# PCB_SCH_Left_Sub.net
KiCad netlist of a schematic drawn in EasyEDA Pro
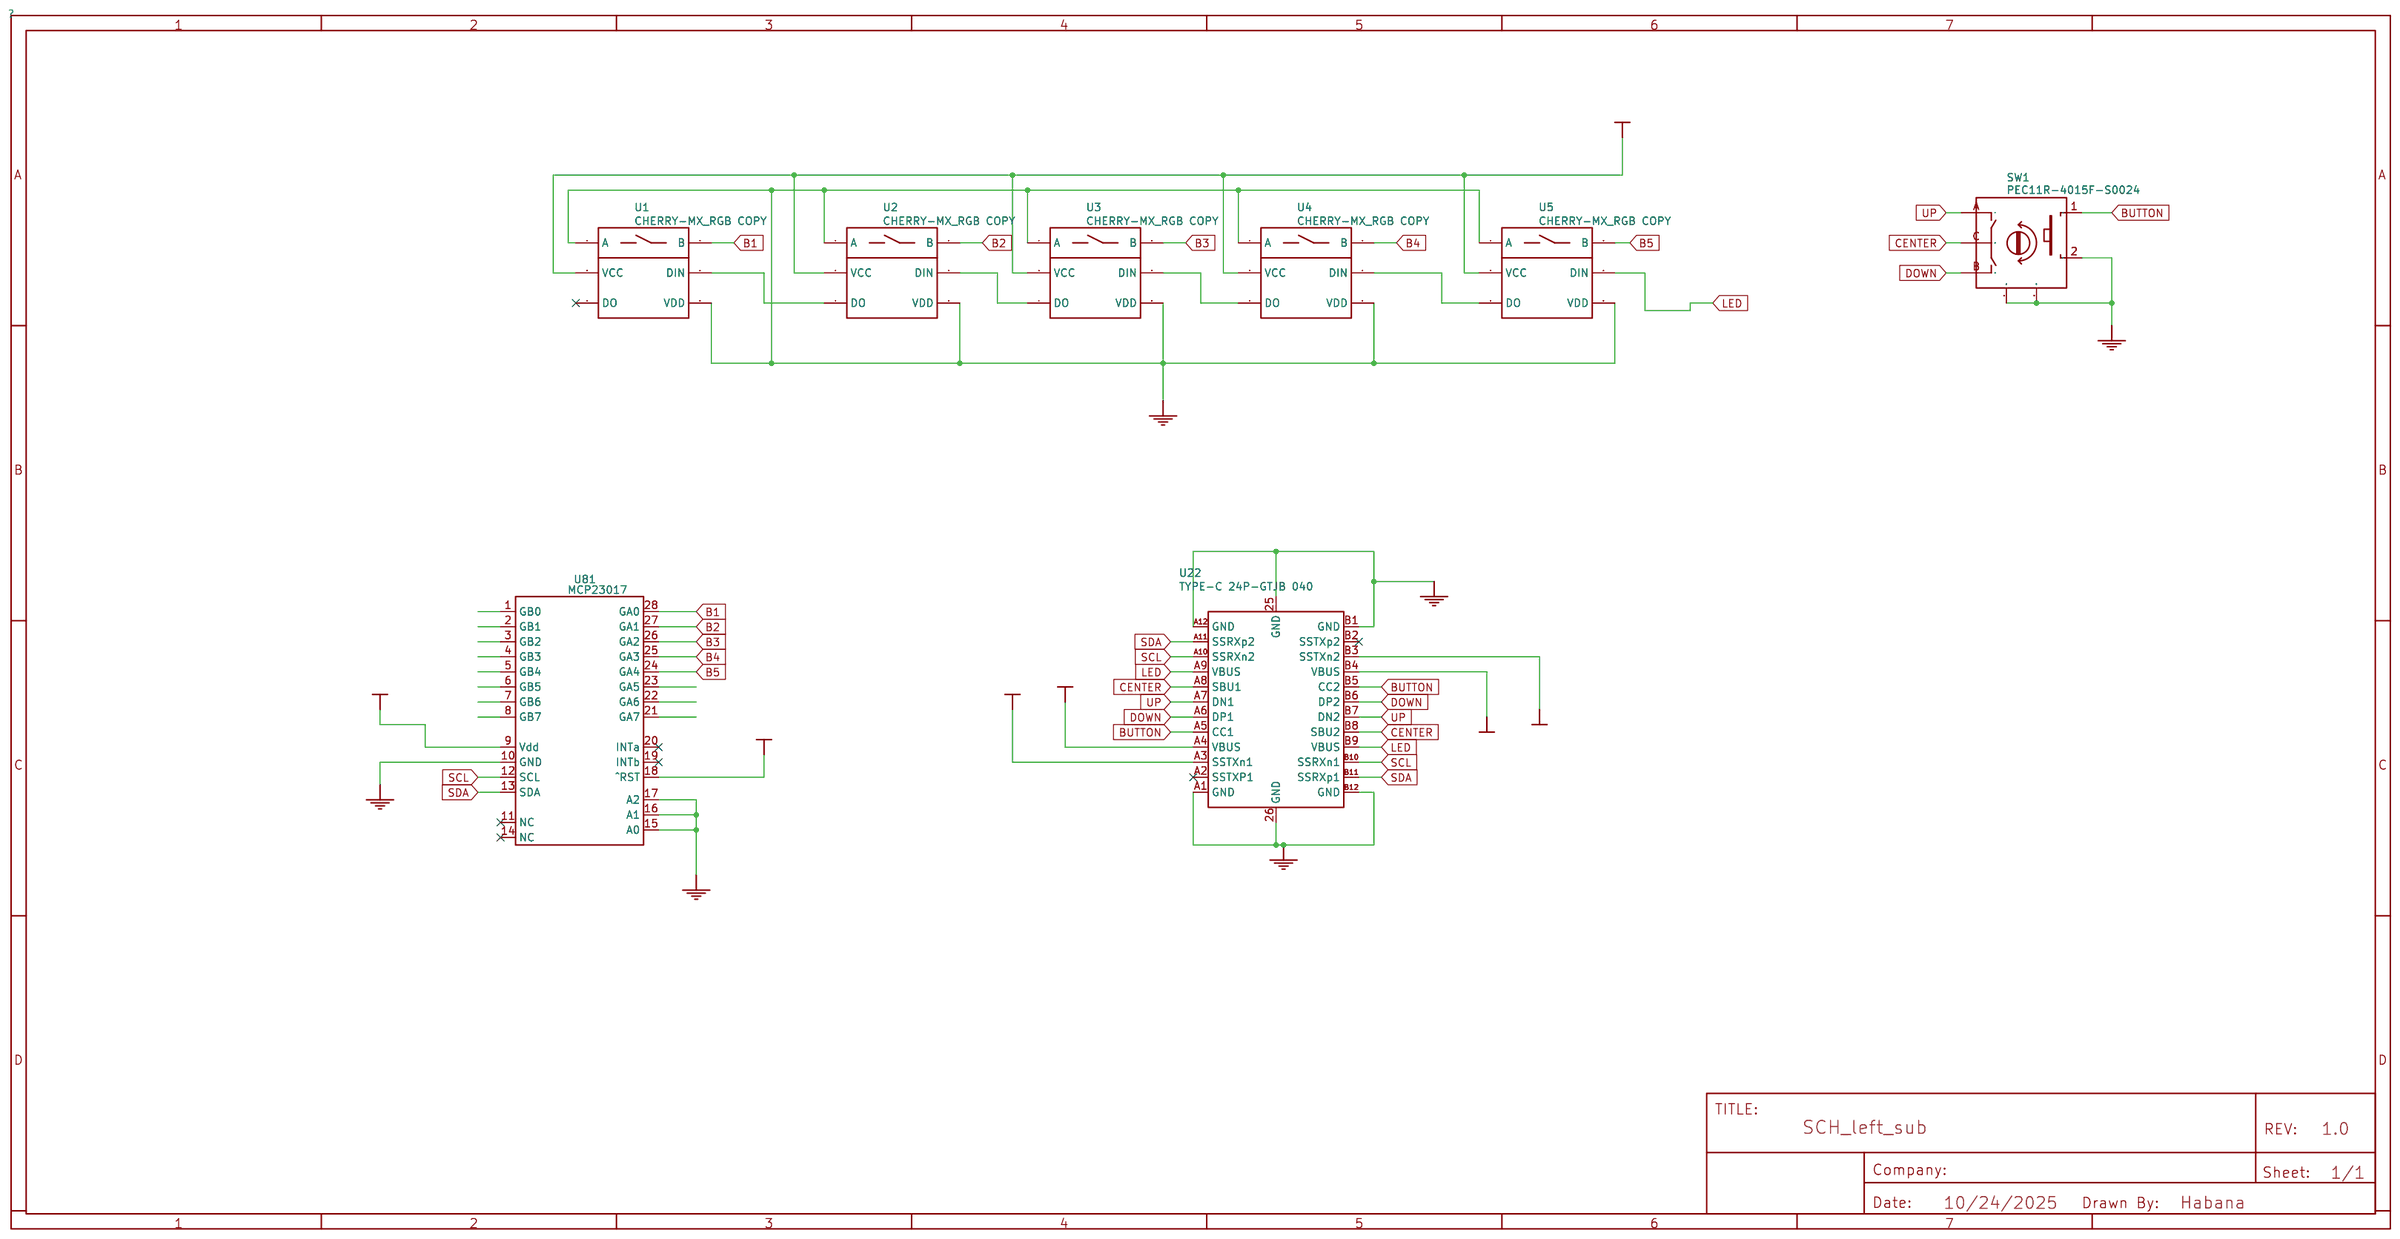
[diagram p0: schematic sheet]

(export (version "E")
  (design (tool "Eeschema 10.0.6"))
  (components
    (comp (ref "SW1")
      (value "PEC11R-4015F-S0024")
      (footprint "easyedapro:SW-TH_PEC11R-4XXXF-SXXXX")
      (fields (field (name "Manufacturer") "BOURNS") (field (name "Contributor") "LCSC"))
      (libsource (lib "easyedapro") (part "PEC11R-4015F-S0024"))
    )
    (comp (ref "U1")
      (value "CHERRY-MX_RGB COPY")
      (fields (field (name "Contributor") "unrealin01"))
      (libsource (lib "easyedapro") (part "CHERRY-MX_RGB COPY"))
    )
    (comp (ref "U2")
      (value "CHERRY-MX_RGB COPY")
      (fields (field (name "Contributor") "unrealin01"))
      (libsource (lib "easyedapro") (part "CHERRY-MX_RGB COPY"))
    )
    (comp (ref "U3")
      (value "CHERRY-MX_RGB COPY")
      (fields (field (name "Contributor") "unrealin01"))
      (libsource (lib "easyedapro") (part "CHERRY-MX_RGB COPY"))
    )
    (comp (ref "U4")
      (value "CHERRY-MX_RGB COPY")
      (fields (field (name "Contributor") "unrealin01"))
      (libsource (lib "easyedapro") (part "CHERRY-MX_RGB COPY"))
    )
    (comp (ref "U5")
      (value "CHERRY-MX_RGB COPY")
      (fields (field (name "Contributor") "unrealin01"))
      (libsource (lib "easyedapro") (part "CHERRY-MX_RGB COPY"))
    )
    (comp (ref "U22")
      (value "TYPE-C 24P-GTJB 040")
      (footprint "easyedapro:USB-C-SMD_TYPE-C-24P-GTJB-040")
      (fields (field (name "Manufacturer") "SHOU HAN(首韩)") (field (name "Contributor") "lcsc"))
      (libsource (lib "easyedapro") (part "TYPE-C 24P-GTJB 040"))
    )
    (comp (ref "U81")
      (value "MCP23017")
      (fields (field (name "Contributor") "tsvstar"))
      (libsource (lib "easyedapro") (part "MCP23017"))
    )
  )
  (nets
    (net (code "1") (name "+5V") (class "Default")
      (node (ref "U1") (pin "3") (pinfunction "VCC_3") (pintype "unspecified"))
      (node (ref "U2") (pin "3") (pinfunction "VCC_3") (pintype "unspecified"))
      (node (ref "U22") (pin "A4") (pinfunction "VBUS_A4") (pintype "unspecified"))
      (node (ref "U22") (pin "B4") (pinfunction "VBUS_B4") (pintype "unspecified"))
      (node (ref "U3") (pin "3") (pinfunction "VCC_3") (pintype "unspecified"))
      (node (ref "U4") (pin "3") (pinfunction "VCC_3") (pintype "unspecified"))
      (node (ref "U5") (pin "3") (pinfunction "VCC_3") (pintype "unspecified"))
    )
    (net (code "2") (name "B1") (class "Default")
      (node (ref "U1") (pin "2") (pinfunction "B_2") (pintype "unspecified"))
      (node (ref "U81") (pin "28") (pinfunction "GA0_28") (pintype "unspecified"))
    )
    (net (code "3") (name "B2") (class "Default")
      (node (ref "U2") (pin "2") (pinfunction "B_2") (pintype "unspecified"))
      (node (ref "U81") (pin "27") (pinfunction "GA1_27") (pintype "unspecified"))
    )
    (net (code "4") (name "B3") (class "Default")
      (node (ref "U3") (pin "2") (pinfunction "B_2") (pintype "unspecified"))
      (node (ref "U81") (pin "26") (pinfunction "GA2_26") (pintype "unspecified"))
    )
    (net (code "5") (name "B4") (class "Default")
      (node (ref "U4") (pin "2") (pinfunction "B_2") (pintype "unspecified"))
      (node (ref "U81") (pin "25") (pinfunction "GA3_25") (pintype "unspecified"))
    )
    (net (code "6") (name "B5") (class "Default")
      (node (ref "U5") (pin "2") (pinfunction "B_2") (pintype "unspecified"))
      (node (ref "U81") (pin "24") (pinfunction "GA4_24") (pintype "unspecified"))
    )
    (net (code "7") (name "BUTTON") (class "Default")
      (node (ref "SW1") (pin "1") (pinfunction "1_1") (pintype "unspecified"))
      (node (ref "U22") (pin "A5") (pinfunction "CC1_A5") (pintype "unspecified"))
      (node (ref "U22") (pin "B5") (pinfunction "CC2_B5") (pintype "unspecified"))
    )
    (net (code "8") (name "CENTER") (class "Default")
      (node (ref "SW1") (pin "C") (pinfunction "C_C") (pintype "unspecified"))
      (node (ref "U22") (pin "A8") (pinfunction "SBU1_A8") (pintype "unspecified"))
      (node (ref "U22") (pin "B8") (pinfunction "SBU2_B8") (pintype "unspecified"))
    )
    (net (code "9") (name "DOWN") (class "Default")
      (node (ref "SW1") (pin "B") (pinfunction "B_B") (pintype "unspecified"))
      (node (ref "U22") (pin "A6") (pinfunction "DP1_A6") (pintype "unspecified"))
      (node (ref "U22") (pin "B6") (pinfunction "DP2_B6") (pintype "unspecified"))
    )
    (net (code "10") (name "GND") (class "Default")
      (node (ref "SW1") (pin "2") (pinfunction "2_2") (pintype "unspecified"))
      (node (ref "SW1") (pin "MT1") (pinfunction "MT1_MT1") (pintype "unspecified"))
      (node (ref "SW1") (pin "MT2") (pinfunction "MT2_MT2") (pintype "unspecified"))
      (node (ref "U1") (pin "1") (pinfunction "A_1") (pintype "unspecified"))
      (node (ref "U1") (pin "5") (pinfunction "VDD_5") (pintype "unspecified"))
      (node (ref "U2") (pin "1") (pinfunction "A_1") (pintype "unspecified"))
      (node (ref "U2") (pin "5") (pinfunction "VDD_5") (pintype "unspecified"))
      (node (ref "U22") (pin "25") (pinfunction "GND_25") (pintype "unspecified"))
      (node (ref "U22") (pin "26") (pinfunction "GND_26") (pintype "unspecified"))
      (node (ref "U22") (pin "A1") (pinfunction "GND_A1") (pintype "unspecified"))
      (node (ref "U22") (pin "A12") (pinfunction "GND_A12") (pintype "unspecified"))
      (node (ref "U22") (pin "B1") (pinfunction "GND_B1") (pintype "unspecified"))
      (node (ref "U22") (pin "B12") (pinfunction "GND_B12") (pintype "unspecified"))
      (node (ref "U3") (pin "1") (pinfunction "A_1") (pintype "unspecified"))
      (node (ref "U3") (pin "5") (pinfunction "VDD_5") (pintype "unspecified"))
      (node (ref "U4") (pin "1") (pinfunction "A_1") (pintype "unspecified"))
      (node (ref "U4") (pin "5") (pinfunction "VDD_5") (pintype "unspecified"))
      (node (ref "U5") (pin "1") (pinfunction "A_1") (pintype "unspecified"))
      (node (ref "U5") (pin "5") (pinfunction "VDD_5") (pintype "unspecified"))
      (node (ref "U81") (pin "10") (pinfunction "GND_10") (pintype "unspecified"))
      (node (ref "U81") (pin "15") (pinfunction "A0_15") (pintype "unspecified"))
      (node (ref "U81") (pin "16") (pinfunction "A1_16") (pintype "unspecified"))
      (node (ref "U81") (pin "17") (pinfunction "A2_17") (pintype "unspecified"))
    )
    (net (code "11") (name "LED") (class "Default")
      (node (ref "U22") (pin "A9") (pinfunction "VBUS_A9") (pintype "unspecified"))
      (node (ref "U22") (pin "B9") (pinfunction "VBUS_B9") (pintype "unspecified"))
      (node (ref "U5") (pin "6") (pinfunction "DIN_6") (pintype "unspecified"))
    )
    (net (code "12") (name "Net-(U1-DIN)") (class "Default")
      (node (ref "U1") (pin "6") (pinfunction "DIN_6") (pintype "unspecified"))
      (node (ref "U2") (pin "4") (pinfunction "DO_4") (pintype "unspecified"))
    )
    (net (code "13") (name "Net-(U2-DIN)") (class "Default")
      (node (ref "U2") (pin "6") (pinfunction "DIN_6") (pintype "unspecified"))
      (node (ref "U3") (pin "4") (pinfunction "DO_4") (pintype "unspecified"))
    )
    (net (code "14") (name "Net-(U3-DIN)") (class "Default")
      (node (ref "U3") (pin "6") (pinfunction "DIN_6") (pintype "unspecified"))
      (node (ref "U4") (pin "4") (pinfunction "DO_4") (pintype "unspecified"))
    )
    (net (code "15") (name "Net-(U4-DIN)") (class "Default")
      (node (ref "U4") (pin "6") (pinfunction "DIN_6") (pintype "unspecified"))
      (node (ref "U5") (pin "4") (pinfunction "DO_4") (pintype "unspecified"))
    )
    (net (code "16") (name "SCL") (class "Default")
      (node (ref "U22") (pin "A10") (pinfunction "SSRXn2_A10") (pintype "unspecified"))
      (node (ref "U22") (pin "B10") (pinfunction "SSRXn1_B10") (pintype "unspecified"))
      (node (ref "U81") (pin "12") (pinfunction "SCL_12") (pintype "unspecified"))
    )
    (net (code "17") (name "SDA") (class "Default")
      (node (ref "U22") (pin "A11") (pinfunction "SSRXp2_A11") (pintype "unspecified"))
      (node (ref "U22") (pin "B11") (pinfunction "SSRXp1_B11") (pintype "unspecified"))
      (node (ref "U81") (pin "13") (pinfunction "SDA_13") (pintype "unspecified"))
    )
    (net (code "18") (name "UP") (class "Default")
      (node (ref "SW1") (pin "A") (pinfunction "A_A") (pintype "unspecified"))
      (node (ref "U22") (pin "A7") (pinfunction "DN1_A7") (pintype "unspecified"))
      (node (ref "U22") (pin "B7") (pinfunction "DN2_B7") (pintype "unspecified"))
    )
    (net (code "19") (name "VCC") (class "Default")
      (node (ref "U22") (pin "A3") (pinfunction "SSTXn1_A3") (pintype "unspecified"))
      (node (ref "U22") (pin "B3") (pinfunction "SSTXn2_B3") (pintype "unspecified"))
      (node (ref "U81") (pin "18") (pinfunction "^RST_18") (pintype "unspecified"))
      (node (ref "U81") (pin "9") (pinfunction "Vdd_9") (pintype "unspecified"))
    )
    (net (code "20") (name "unconnected-(U1-DO-Pad4)") (class "Default")
      (node (ref "U1") (pin "4") (pinfunction "DO_4") (pintype "unspecified+no_connect"))
    )
    (net (code "21") (name "unconnected-(U22-SSTXP1-PadA2)") (class "Default")
      (node (ref "U22") (pin "A2") (pinfunction "SSTXP1_A2") (pintype "unspecified+no_connect"))
    )
    (net (code "22") (name "unconnected-(U22-SSTXp2-PadB2)") (class "Default")
      (node (ref "U22") (pin "B2") (pinfunction "SSTXp2_B2") (pintype "unspecified+no_connect"))
    )
    (net (code "23") (name "unconnected-(U81-GA5-Pad23)") (class "Default")
      (node (ref "U81") (pin "23") (pinfunction "GA5_23") (pintype "unspecified"))
    )
    (net (code "24") (name "unconnected-(U81-GA6-Pad22)") (class "Default")
      (node (ref "U81") (pin "22") (pinfunction "GA6_22") (pintype "unspecified"))
    )
    (net (code "25") (name "unconnected-(U81-GA7-Pad21)") (class "Default")
      (node (ref "U81") (pin "21") (pinfunction "GA7_21") (pintype "unspecified"))
    )
    (net (code "26") (name "unconnected-(U81-GB0-Pad1)") (class "Default")
      (node (ref "U81") (pin "1") (pinfunction "GB0_1") (pintype "unspecified"))
    )
    (net (code "27") (name "unconnected-(U81-GB1-Pad2)") (class "Default")
      (node (ref "U81") (pin "2") (pinfunction "GB1_2") (pintype "unspecified"))
    )
    (net (code "28") (name "unconnected-(U81-GB2-Pad3)") (class "Default")
      (node (ref "U81") (pin "3") (pinfunction "GB2_3") (pintype "unspecified"))
    )
    (net (code "29") (name "unconnected-(U81-GB3-Pad4)") (class "Default")
      (node (ref "U81") (pin "4") (pinfunction "GB3_4") (pintype "unspecified"))
    )
    (net (code "30") (name "unconnected-(U81-GB4-Pad5)") (class "Default")
      (node (ref "U81") (pin "5") (pinfunction "GB4_5") (pintype "unspecified"))
    )
    (net (code "31") (name "unconnected-(U81-GB5-Pad6)") (class "Default")
      (node (ref "U81") (pin "6") (pinfunction "GB5_6") (pintype "unspecified"))
    )
    (net (code "32") (name "unconnected-(U81-GB6-Pad7)") (class "Default")
      (node (ref "U81") (pin "7") (pinfunction "GB6_7") (pintype "unspecified"))
    )
    (net (code "33") (name "unconnected-(U81-GB7-Pad8)") (class "Default")
      (node (ref "U81") (pin "8") (pinfunction "GB7_8") (pintype "unspecified"))
    )
    (net (code "34") (name "unconnected-(U81-INTa-Pad20)") (class "Default")
      (node (ref "U81") (pin "20") (pinfunction "INTa_20") (pintype "unspecified+no_connect"))
    )
    (net (code "35") (name "unconnected-(U81-INTb-Pad19)") (class "Default")
      (node (ref "U81") (pin "19") (pinfunction "INTb_19") (pintype "unspecified+no_connect"))
    )
    (net (code "36") (name "unconnected-(U81-NC-Pad11)") (class "Default")
      (node (ref "U81") (pin "11") (pinfunction "NC_11") (pintype "unspecified+no_connect"))
    )
    (net (code "37") (name "unconnected-(U81-NC-Pad14)") (class "Default")
      (node (ref "U81") (pin "14") (pinfunction "NC_14") (pintype "unspecified+no_connect"))
    )
  )
)
